# PanelBotones.net
KiCad netlist of a schematic drawn in EAGLE
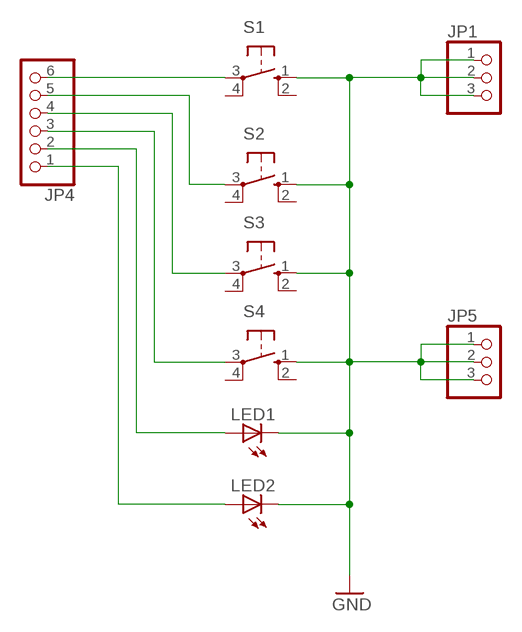
[diagram p0: schematic, sheet 1]

(export (version "E")
  (design (tool "Eeschema 10.0.6"))
  (components
    (comp (ref "JP1")
      (value "PINHD-1X3")
      (footprint "eagle-import:1X03")
      (libsource (lib "eagle-import") (part "PINHD-1X3"))
    )
    (comp (ref "JP4")
      (value "PINHD-1X6")
      (footprint "eagle-import:1X06")
      (libsource (lib "eagle-import") (part "PINHD-1X6"))
    )
    (comp (ref "JP5")
      (value "PINHD-1X3")
      (footprint "eagle-import:1X03")
      (libsource (lib "eagle-import") (part "PINHD-1X3"))
    )
    (comp (ref "LED1")
      (value "LED3MM")
      (footprint "eagle-import:LED3MM")
      (libsource (lib "eagle-import") (part "LED3MM"))
    )
    (comp (ref "LED2")
      (value "LED3MM")
      (footprint "eagle-import:LED3MM")
      (libsource (lib "eagle-import") (part "LED3MM"))
    )
    (comp (ref "S1")
      (value "10-XX")
      (footprint "eagle-import:B3F-10XX")
      (fields (field (name "MPN") "B3F-1000"))
      (libsource (lib "eagle-import") (part "10-XX"))
    )
    (comp (ref "S2")
      (value "10-XX")
      (footprint "eagle-import:B3F-10XX")
      (fields (field (name "MPN") "B3F-1000"))
      (libsource (lib "eagle-import") (part "10-XX"))
    )
    (comp (ref "S3")
      (value "10-XX")
      (footprint "eagle-import:B3F-10XX")
      (fields (field (name "MPN") "B3F-1000"))
      (libsource (lib "eagle-import") (part "10-XX"))
    )
    (comp (ref "S4")
      (value "10-XX")
      (footprint "eagle-import:B3F-10XX")
      (fields (field (name "MPN") "B3F-1000"))
      (libsource (lib "eagle-import") (part "10-XX"))
    )
  )
  (nets
    (net (code "1") (name "GND") (class "Default")
      (node (ref "JP1") (pin "1") (pinfunction "1_1") (pintype "passive"))
      (node (ref "JP1") (pin "2") (pinfunction "2_2") (pintype "passive"))
      (node (ref "JP1") (pin "3") (pinfunction "3_3") (pintype "passive"))
      (node (ref "JP5") (pin "1") (pinfunction "1_1") (pintype "passive"))
      (node (ref "JP5") (pin "2") (pinfunction "2_2") (pintype "passive"))
      (node (ref "JP5") (pin "3") (pinfunction "3_3") (pintype "passive"))
      (node (ref "LED1") (pin "K") (pinfunction "C_K") (pintype "passive"))
      (node (ref "LED2") (pin "K") (pinfunction "C_K") (pintype "passive"))
      (node (ref "S1") (pin "1") (pinfunction "S_1") (pintype "passive"))
      (node (ref "S2") (pin "1") (pinfunction "S_1") (pintype "passive"))
      (node (ref "S3") (pin "1") (pinfunction "S_1") (pintype "passive"))
      (node (ref "S4") (pin "1") (pinfunction "S_1") (pintype "passive"))
    )
    (net (code "2") (name "Net-(JP4-Pad1)") (class "Default")
      (node (ref "JP4") (pin "1") (pinfunction "1_1") (pintype "passive"))
      (node (ref "LED2") (pin "A") (pinfunction "A_A") (pintype "passive"))
    )
    (net (code "3") (name "Net-(JP4-Pad2)") (class "Default")
      (node (ref "JP4") (pin "2") (pinfunction "2_2") (pintype "passive"))
      (node (ref "LED1") (pin "A") (pinfunction "A_A") (pintype "passive"))
    )
    (net (code "4") (name "Net-(S1-P)") (class "Default")
      (node (ref "JP4") (pin "6") (pinfunction "6_6") (pintype "passive"))
      (node (ref "S1") (pin "3") (pinfunction "P_3") (pintype "passive"))
    )
    (net (code "5") (name "Net-(S2-P)") (class "Default")
      (node (ref "JP4") (pin "5") (pinfunction "5_5") (pintype "passive"))
      (node (ref "S2") (pin "3") (pinfunction "P_3") (pintype "passive"))
    )
    (net (code "6") (name "Net-(S3-P)") (class "Default")
      (node (ref "JP4") (pin "4") (pinfunction "4_4") (pintype "passive"))
      (node (ref "S3") (pin "3") (pinfunction "P_3") (pintype "passive"))
    )
    (net (code "7") (name "Net-(S4-P)") (class "Default")
      (node (ref "JP4") (pin "3") (pinfunction "3_3") (pintype "passive"))
      (node (ref "S4") (pin "3") (pinfunction "P_3") (pintype "passive"))
    )
    (net (code "8") (name "unconnected-(S1-P1-Pad4)") (class "Default")
      (node (ref "S1") (pin "4") (pinfunction "P1_4") (pintype "passive"))
    )
    (net (code "9") (name "unconnected-(S1-S1-Pad2)") (class "Default")
      (node (ref "S1") (pin "2") (pinfunction "S1_2") (pintype "passive"))
    )
    (net (code "10") (name "unconnected-(S2-P1-Pad4)") (class "Default")
      (node (ref "S2") (pin "4") (pinfunction "P1_4") (pintype "passive"))
    )
    (net (code "11") (name "unconnected-(S2-S1-Pad2)") (class "Default")
      (node (ref "S2") (pin "2") (pinfunction "S1_2") (pintype "passive"))
    )
    (net (code "12") (name "unconnected-(S3-P1-Pad4)") (class "Default")
      (node (ref "S3") (pin "4") (pinfunction "P1_4") (pintype "passive"))
    )
    (net (code "13") (name "unconnected-(S3-S1-Pad2)") (class "Default")
      (node (ref "S3") (pin "2") (pinfunction "S1_2") (pintype "passive"))
    )
    (net (code "14") (name "unconnected-(S4-P1-Pad4)") (class "Default")
      (node (ref "S4") (pin "4") (pinfunction "P1_4") (pintype "passive"))
    )
    (net (code "15") (name "unconnected-(S4-S1-Pad2)") (class "Default")
      (node (ref "S4") (pin "2") (pinfunction "S1_2") (pintype "passive"))
    )
  )
)
